# esquema_v4.net
KiCad netlist of a schematic drawn in EAGLE
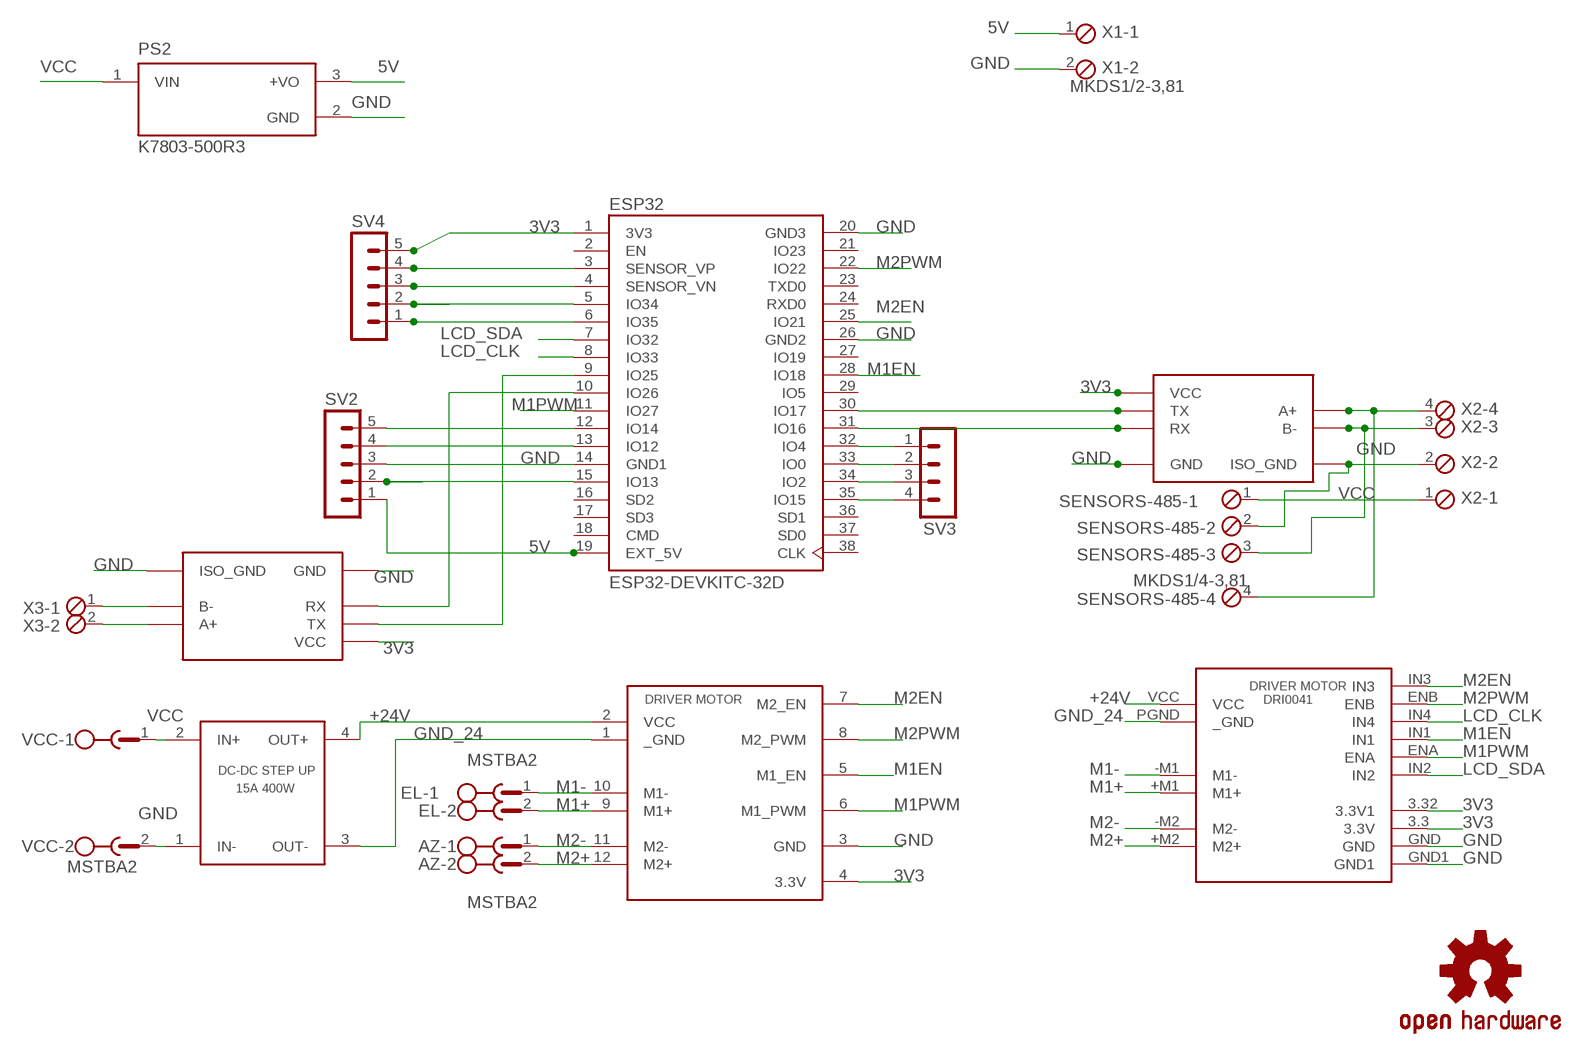
[diagram p0: schematic, sheet 1]

(export (version "E")
  (design (tool "Eeschema 10.0.6"))
  (components
    (comp (ref "AZ")
      (value "MSTBA2")
      (footprint "eagle-import:MSTBA2")
      (fields (field (name "MF") "FARNELL") (field (name "MPN") "1757242"))
      (libsource (lib "eagle-import") (part "MSTBA2"))
    )
    (comp (ref "EL")
      (value "MSTBA2")
      (footprint "eagle-import:MSTBA2")
      (fields (field (name "MF") "FARNELL") (field (name "MPN") "1757242"))
      (libsource (lib "eagle-import") (part "MSTBA2"))
    )
    (comp (ref "ESP32")
      (value "ESP32-DEVKITC-32D")
      (footprint "eagle-import:MODULE_ESP32-DEVKITC-32D")
      (fields (field (name "MF") "Espressif Systems"))
      (libsource (lib "eagle-import") (part "ESP32-DEVKITC-32D"))
    )
    (comp (ref "LOGO1")
      (value "OSHW-LOGOMINI")
      (footprint "eagle-import:OSHW-LOGO-MINI")
      (libsource (lib "eagle-import") (part "OSHW-LOGOMINI"))
    )
    (comp (ref "M1")
      (value "DRIVER_MOTOR")
      (footprint "eagle-import:DRIVER_MOTOR")
      (libsource (lib "eagle-import") (part "DRIVER_MOTOR"))
    )
    (comp (ref "M2")
      (value "DC-DC_STRP_UP")
      (footprint "eagle-import:DC-DC-SETP-UP")
      (libsource (lib "eagle-import") (part "DC-DC_STRP_UP"))
    )
    (comp (ref "M3")
      (value "LIMNOTECH_SMC_RS485")
      (footprint "eagle-import:LIMNOTECH_SMC_RS485")
      (libsource (lib "eagle-import") (part "LIMNOTECH_SMC_RS485"))
    )
    (comp (ref "M4")
      (value "LIMNOTECH_SMC_RS485")
      (footprint "eagle-import:LIMNOTECH_SMC_RS485")
      (libsource (lib "eagle-import") (part "LIMNOTECH_SMC_RS485"))
    )
    (comp (ref "PS2")
      (value "K7803-500R3")
      (footprint "eagle-import:CONV_K7803-500R3")
      (fields (field (name "MF") "Mornsun America, LLC"))
      (libsource (lib "eagle-import") (part "K7803-500R3"))
    )
    (comp (ref "SENSORS-485")
      (value "MKDS1/4-3,81")
      (footprint "eagle-import:4POL381")
      (libsource (lib "eagle-import") (part "MKDS1/4-3,81"))
    )
    (comp (ref "SV2")
      (value "MA05-1")
      (footprint "eagle-import:MA05-1")
      (libsource (lib "eagle-import") (part "MA05-1"))
    )
    (comp (ref "SV3")
      (value "MA04-1")
      (footprint "eagle-import:MA04-1")
      (libsource (lib "eagle-import") (part "MA04-1"))
    )
    (comp (ref "SV4")
      (value "MA05-1")
      (footprint "eagle-import:MA05-1")
      (libsource (lib "eagle-import") (part "MA05-1"))
    )
    (comp (ref "U$2")
      (value "DRIVER_DRI0041")
      (footprint "eagle-import:DRI0041")
      (libsource (lib "eagle-import") (part "DRIVER_DRI0041"))
    )
    (comp (ref "VCC")
      (value "MSTBA2")
      (footprint "eagle-import:MSTBA2")
      (fields (field (name "MF") "FARNELL") (field (name "MPN") "1757242"))
      (libsource (lib "eagle-import") (part "MSTBA2"))
    )
    (comp (ref "X1")
      (value "MKDS1/2-3,81")
      (footprint "eagle-import:2POL381")
      (libsource (lib "eagle-import") (part "MKDS1/2-3,81"))
    )
    (comp (ref "X2")
      (value "MKDS1/4-3,81")
      (footprint "eagle-import:4POL381")
      (libsource (lib "eagle-import") (part "MKDS1/4-3,81"))
    )
    (comp (ref "X3")
      (value "MKDS1/2-3,81")
      (footprint "eagle-import:2POL381")
      (libsource (lib "eagle-import") (part "MKDS1/2-3,81"))
    )
  )
  (nets
    (net (code "1") (name "/+24V") (class "Default")
      (node (ref "M1") (pin "2") (pinfunction "VCC_2") (pintype "bidirectional"))
      (node (ref "M2") (pin "4") (pinfunction "OUT+_4") (pintype "bidirectional"))
      (node (ref "U$2") (pin "VCC") (pinfunction "VCC_VCC") (pintype "bidirectional"))
    )
    (net (code "2") (name "/3V3") (class "Default")
      (node (ref "ESP32") (pin "1") (pinfunction "3V3_1") (pintype "power_in"))
      (node (ref "M1") (pin "4") (pinfunction "3.3V_4") (pintype "bidirectional"))
      (node (ref "M3") (pin "VCC") (pinfunction "VCC_VCC") (pintype "bidirectional"))
      (node (ref "M4") (pin "VCC") (pinfunction "VCC_VCC") (pintype "bidirectional"))
      (node (ref "SV4") (pin "5") (pinfunction "5_5") (pintype "passive"))
      (node (ref "U$2") (pin "3.3") (pinfunction "3.3V_3.3") (pintype "bidirectional"))
      (node (ref "U$2") (pin "3.32") (pinfunction "3.3V1_3.32") (pintype "bidirectional"))
    )
    (net (code "3") (name "/5V") (class "Default")
      (node (ref "ESP32") (pin "19") (pinfunction "EXT_5V_19") (pintype "power_in"))
      (node (ref "PS2") (pin "3") (pinfunction "+VO_3") (pintype "output"))
      (node (ref "SV2") (pin "1") (pinfunction "1_1") (pintype "passive"))
      (node (ref "X1") (pin "1") (pinfunction "1_1") (pintype "passive"))
    )
    (net (code "4") (name "/GND") (class "Default")
      (node (ref "ESP32") (pin "14") (pinfunction "GND1_14") (pintype "power_in"))
      (node (ref "ESP32") (pin "20") (pinfunction "GND3_20") (pintype "power_in"))
      (node (ref "ESP32") (pin "26") (pinfunction "GND2_26") (pintype "power_in"))
      (node (ref "M1") (pin "3") (pinfunction "GND_3") (pintype "bidirectional"))
      (node (ref "M2") (pin "1") (pinfunction "IN-_1") (pintype "bidirectional"))
      (node (ref "M3") (pin "GND") (pinfunction "GND_GND") (pintype "bidirectional"))
      (node (ref "M3") (pin "GND_ISO") (pinfunction "ISO_GND_GND_ISO") (pintype "bidirectional"))
      (node (ref "M4") (pin "GND") (pinfunction "GND_GND") (pintype "bidirectional"))
      (node (ref "M4") (pin "GND_ISO") (pinfunction "ISO_GND_GND_ISO") (pintype "bidirectional"))
      (node (ref "PS2") (pin "2") (pinfunction "GND_2") (pintype "power_in"))
      (node (ref "SENSORS-485") (pin "2") (pinfunction "1_2") (pintype "passive"))
      (node (ref "SV2") (pin "3") (pinfunction "3_3") (pintype "passive"))
      (node (ref "U$2") (pin "GND") (pinfunction "GND_GND") (pintype "bidirectional"))
      (node (ref "U$2") (pin "GND1") (pinfunction "GND1_GND1") (pintype "bidirectional"))
      (node (ref "VCC") (pin "2") (pinfunction "1_2") (pintype "passive"))
      (node (ref "X1") (pin "2") (pinfunction "1_2") (pintype "passive"))
      (node (ref "X2") (pin "2") (pinfunction "1_2") (pintype "passive"))
    )
    (net (code "5") (name "/GND_24") (class "Default")
      (node (ref "M1") (pin "1") (pinfunction "_GND_1") (pintype "bidirectional"))
      (node (ref "M2") (pin "3") (pinfunction "OUT-_3") (pintype "bidirectional"))
      (node (ref "U$2") (pin "PGND") (pinfunction "_GND_PGND") (pintype "bidirectional"))
    )
    (net (code "6") (name "/LCD_CLK") (class "Default")
      (node (ref "ESP32") (pin "8") (pinfunction "IO33_8") (pintype "bidirectional"))
      (node (ref "U$2") (pin "IN4") (pinfunction "IN4_IN4") (pintype "bidirectional"))
    )
    (net (code "7") (name "/LCD_SDA") (class "Default")
      (node (ref "ESP32") (pin "7") (pinfunction "IO32_7") (pintype "bidirectional"))
      (node (ref "U$2") (pin "IN2") (pinfunction "IN2_IN2") (pintype "bidirectional"))
    )
    (net (code "8") (name "/M1+") (class "Default")
      (node (ref "EL") (pin "2") (pinfunction "1_2") (pintype "passive"))
      (node (ref "M1") (pin "9") (pinfunction "M1+_9") (pintype "bidirectional"))
      (node (ref "U$2") (pin "+M1") (pinfunction "M1+_+M1") (pintype "bidirectional"))
    )
    (net (code "9") (name "/M1-") (class "Default")
      (node (ref "EL") (pin "1") (pinfunction "1_1") (pintype "passive"))
      (node (ref "M1") (pin "10") (pinfunction "M1-_10") (pintype "bidirectional"))
      (node (ref "U$2") (pin "-M1") (pinfunction "M1-_-M1") (pintype "bidirectional"))
    )
    (net (code "10") (name "/M1EN") (class "Default")
      (node (ref "ESP32") (pin "28") (pinfunction "IO18_28") (pintype "bidirectional"))
      (node (ref "M1") (pin "5") (pinfunction "M1_EN_5") (pintype "bidirectional"))
      (node (ref "U$2") (pin "IN1") (pinfunction "IN1_IN1") (pintype "bidirectional"))
    )
    (net (code "11") (name "/M1PWM") (class "Default")
      (node (ref "ESP32") (pin "11") (pinfunction "IO27_11") (pintype "bidirectional"))
      (node (ref "M1") (pin "6") (pinfunction "M1_PWM_6") (pintype "bidirectional"))
      (node (ref "U$2") (pin "ENA") (pinfunction "ENA_ENA") (pintype "bidirectional"))
    )
    (net (code "12") (name "/M2+") (class "Default")
      (node (ref "AZ") (pin "2") (pinfunction "1_2") (pintype "passive"))
      (node (ref "M1") (pin "12") (pinfunction "M2+_12") (pintype "bidirectional"))
      (node (ref "U$2") (pin "+M2") (pinfunction "M2+_+M2") (pintype "bidirectional"))
    )
    (net (code "13") (name "/M2-") (class "Default")
      (node (ref "AZ") (pin "1") (pinfunction "1_1") (pintype "passive"))
      (node (ref "M1") (pin "11") (pinfunction "M2-_11") (pintype "bidirectional"))
      (node (ref "U$2") (pin "-M2") (pinfunction "M2-_-M2") (pintype "bidirectional"))
    )
    (net (code "14") (name "/M2EN") (class "Default")
      (node (ref "ESP32") (pin "25") (pinfunction "IO21_25") (pintype "bidirectional"))
      (node (ref "M1") (pin "7") (pinfunction "M2_EN_7") (pintype "bidirectional"))
      (node (ref "U$2") (pin "IN3") (pinfunction "IN3_IN3") (pintype "bidirectional"))
    )
    (net (code "15") (name "/M2PWM") (class "Default")
      (node (ref "ESP32") (pin "22") (pinfunction "IO22_22") (pintype "bidirectional"))
      (node (ref "M1") (pin "8") (pinfunction "M2_PWM_8") (pintype "bidirectional"))
      (node (ref "U$2") (pin "ENB") (pinfunction "ENB_ENB") (pintype "bidirectional"))
    )
    (net (code "16") (name "/VCC") (class "Default")
      (node (ref "M2") (pin "2") (pinfunction "IN+_2") (pintype "bidirectional"))
      (node (ref "PS2") (pin "1") (pinfunction "VIN_1") (pintype "input"))
      (node (ref "SENSORS-485") (pin "1") (pinfunction "1_1") (pintype "passive"))
      (node (ref "VCC") (pin "1") (pinfunction "1_1") (pintype "passive"))
      (node (ref "X2") (pin "1") (pinfunction "1_1") (pintype "passive"))
    )
    (net (code "17") (name "Net-(ESP32-IO0)") (class "Default")
      (node (ref "ESP32") (pin "33") (pinfunction "IO0_33") (pintype "bidirectional"))
      (node (ref "SV3") (pin "2") (pinfunction "2_2") (pintype "passive"))
    )
    (net (code "18") (name "Net-(ESP32-IO2)") (class "Default")
      (node (ref "ESP32") (pin "34") (pinfunction "IO2_34") (pintype "bidirectional"))
      (node (ref "SV3") (pin "3") (pinfunction "3_3") (pintype "passive"))
    )
    (net (code "19") (name "Net-(ESP32-IO4)") (class "Default")
      (node (ref "ESP32") (pin "32") (pinfunction "IO4_32") (pintype "bidirectional"))
      (node (ref "SV3") (pin "1") (pinfunction "1_1") (pintype "passive"))
    )
    (net (code "20") (name "Net-(ESP32-IO12)") (class "Default")
      (node (ref "ESP32") (pin "13") (pinfunction "IO12_13") (pintype "bidirectional"))
      (node (ref "SV2") (pin "4") (pinfunction "4_4") (pintype "passive"))
    )
    (net (code "21") (name "Net-(ESP32-IO13)") (class "Default")
      (node (ref "ESP32") (pin "15") (pinfunction "IO13_15") (pintype "bidirectional"))
      (node (ref "SV2") (pin "2") (pinfunction "2_2") (pintype "passive"))
    )
    (net (code "22") (name "Net-(ESP32-IO14)") (class "Default")
      (node (ref "ESP32") (pin "12") (pinfunction "IO14_12") (pintype "bidirectional"))
      (node (ref "SV2") (pin "5") (pinfunction "5_5") (pintype "passive"))
    )
    (net (code "23") (name "Net-(ESP32-IO15)") (class "Default")
      (node (ref "ESP32") (pin "35") (pinfunction "IO15_35") (pintype "bidirectional"))
      (node (ref "SV3") (pin "4") (pinfunction "4_4") (pintype "passive"))
    )
    (net (code "24") (name "Net-(ESP32-IO16)") (class "Default")
      (node (ref "ESP32") (pin "31") (pinfunction "IO16_31") (pintype "bidirectional"))
      (node (ref "M4") (pin "RX") (pinfunction "RX_RX") (pintype "bidirectional"))
    )
    (net (code "25") (name "Net-(ESP32-IO17)") (class "Default")
      (node (ref "ESP32") (pin "30") (pinfunction "IO17_30") (pintype "bidirectional"))
      (node (ref "M4") (pin "TX") (pinfunction "TX_TX") (pintype "bidirectional"))
    )
    (net (code "26") (name "Net-(ESP32-IO25)") (class "Default")
      (node (ref "ESP32") (pin "9") (pinfunction "IO25_9") (pintype "bidirectional"))
      (node (ref "M3") (pin "TX") (pinfunction "TX_TX") (pintype "bidirectional"))
    )
    (net (code "27") (name "Net-(ESP32-IO26)") (class "Default")
      (node (ref "ESP32") (pin "10") (pinfunction "IO26_10") (pintype "bidirectional"))
      (node (ref "M3") (pin "RX") (pinfunction "RX_RX") (pintype "bidirectional"))
    )
    (net (code "28") (name "Net-(ESP32-IO34)") (class "Default")
      (node (ref "ESP32") (pin "5") (pinfunction "IO34_5") (pintype "bidirectional"))
      (node (ref "SV4") (pin "2") (pinfunction "2_2") (pintype "passive"))
    )
    (net (code "29") (name "Net-(ESP32-IO35)") (class "Default")
      (node (ref "ESP32") (pin "6") (pinfunction "IO35_6") (pintype "bidirectional"))
      (node (ref "SV4") (pin "1") (pinfunction "1_1") (pintype "passive"))
    )
    (net (code "30") (name "Net-(ESP32-SENSOR_VN)") (class "Default")
      (node (ref "ESP32") (pin "4") (pinfunction "SENSOR_VN_4") (pintype "input"))
      (node (ref "SV4") (pin "3") (pinfunction "3_3") (pintype "passive"))
    )
    (net (code "31") (name "Net-(ESP32-SENSOR_VP)") (class "Default")
      (node (ref "ESP32") (pin "3") (pinfunction "SENSOR_VP_3") (pintype "input"))
      (node (ref "SV4") (pin "4") (pinfunction "4_4") (pintype "passive"))
    )
    (net (code "32") (name "Net-(M3-PadB-)") (class "Default")
      (node (ref "M3") (pin "B-") (pinfunction "B-_B-") (pintype "bidirectional"))
      (node (ref "X3") (pin "1") (pinfunction "1_1") (pintype "passive"))
    )
    (net (code "33") (name "Net-(SENSORS-485C-1)") (class "Default")
      (node (ref "M4") (pin "B-") (pinfunction "B-_B-") (pintype "bidirectional"))
      (node (ref "SENSORS-485") (pin "3") (pinfunction "1_3") (pintype "passive"))
      (node (ref "X2") (pin "3") (pinfunction "1_3") (pintype "passive"))
    )
    (net (code "34") (name "Net-(SENSORS-485D-1)") (class "Default")
      (node (ref "M4") (pin "A+") (pinfunction "A+_A+") (pintype "bidirectional"))
      (node (ref "SENSORS-485") (pin "4") (pinfunction "1_4") (pintype "passive"))
      (node (ref "X2") (pin "4") (pinfunction "1_4") (pintype "passive"))
    )
    (net (code "35") (name "Net-(X3B-1)") (class "Default")
      (node (ref "M3") (pin "A+") (pinfunction "A+_A+") (pintype "bidirectional"))
      (node (ref "X3") (pin "2") (pinfunction "1_2") (pintype "passive"))
    )
    (net (code "36") (name "unconnected-(ESP32-CLK-Pad38)") (class "Default")
      (node (ref "ESP32") (pin "38") (pinfunction "CLK_38") (pintype "input"))
    )
    (net (code "37") (name "unconnected-(ESP32-CMD-Pad18)") (class "Default")
      (node (ref "ESP32") (pin "18") (pinfunction "CMD_18") (pintype "bidirectional"))
    )
    (net (code "38") (name "unconnected-(ESP32-EN-Pad2)") (class "Default")
      (node (ref "ESP32") (pin "2") (pinfunction "EN_2") (pintype "input"))
    )
    (net (code "39") (name "unconnected-(ESP32-IO5-Pad29)") (class "Default")
      (node (ref "ESP32") (pin "29") (pinfunction "IO5_29") (pintype "bidirectional"))
    )
    (net (code "40") (name "unconnected-(ESP32-IO19-Pad27)") (class "Default")
      (node (ref "ESP32") (pin "27") (pinfunction "IO19_27") (pintype "bidirectional"))
    )
    (net (code "41") (name "unconnected-(ESP32-IO23-Pad21)") (class "Default")
      (node (ref "ESP32") (pin "21") (pinfunction "IO23_21") (pintype "bidirectional"))
    )
    (net (code "42") (name "unconnected-(ESP32-RXD0-Pad24)") (class "Default")
      (node (ref "ESP32") (pin "24") (pinfunction "RXD0_24") (pintype "input"))
    )
    (net (code "43") (name "unconnected-(ESP32-SD0-Pad37)") (class "Default")
      (node (ref "ESP32") (pin "37") (pinfunction "SD0_37") (pintype "bidirectional"))
    )
    (net (code "44") (name "unconnected-(ESP32-SD1-Pad36)") (class "Default")
      (node (ref "ESP32") (pin "36") (pinfunction "SD1_36") (pintype "bidirectional"))
    )
    (net (code "45") (name "unconnected-(ESP32-SD2-Pad16)") (class "Default")
      (node (ref "ESP32") (pin "16") (pinfunction "SD2_16") (pintype "bidirectional"))
    )
    (net (code "46") (name "unconnected-(ESP32-SD3-Pad17)") (class "Default")
      (node (ref "ESP32") (pin "17") (pinfunction "SD3_17") (pintype "bidirectional"))
    )
    (net (code "47") (name "unconnected-(ESP32-TXD0-Pad23)") (class "Default")
      (node (ref "ESP32") (pin "23") (pinfunction "TXD0_23") (pintype "output"))
    )
  )
)
